# Vario_Kobo_TOP.net
KiCad netlist of a schematic drawn in EAGLE
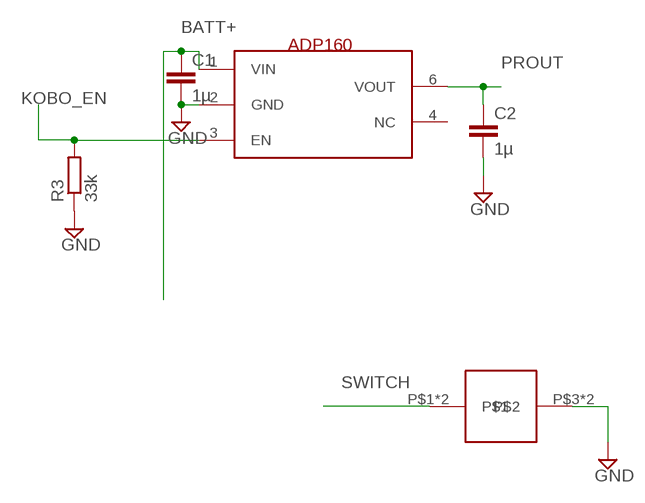
[diagram p0: schematic, sheet 1]
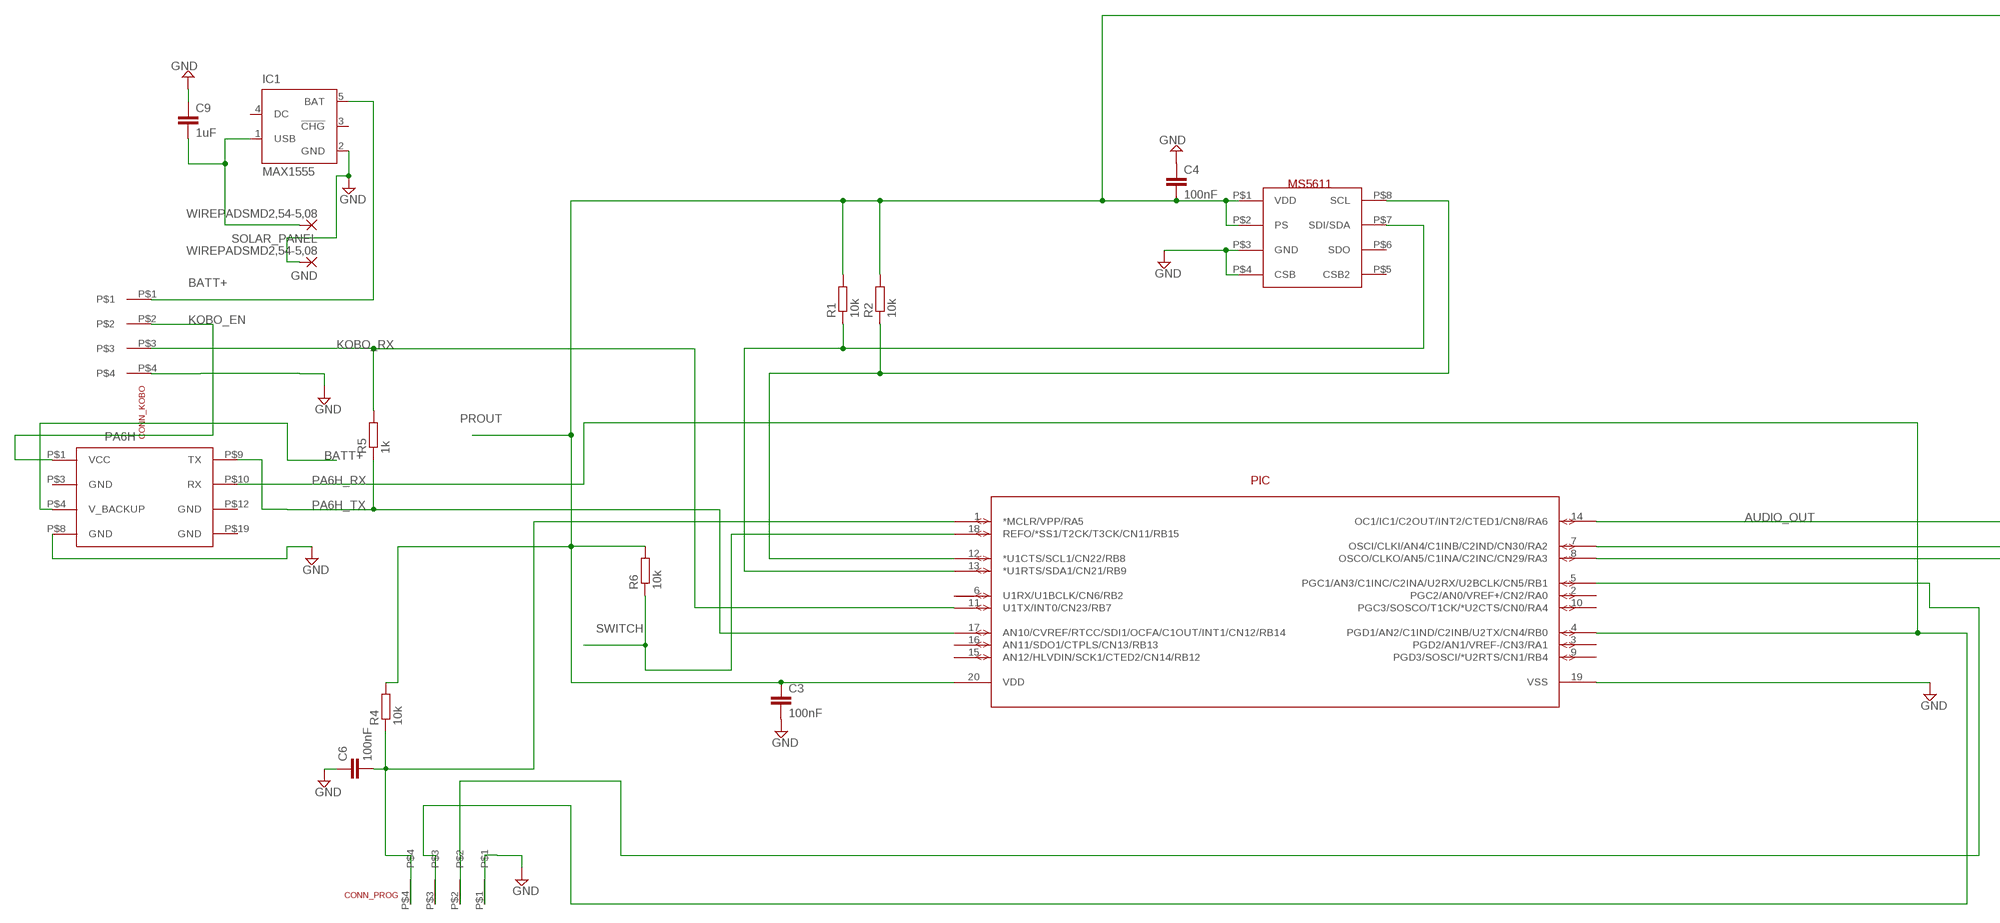
[diagram p1: schematic, sheet 2, part 1 of 2]
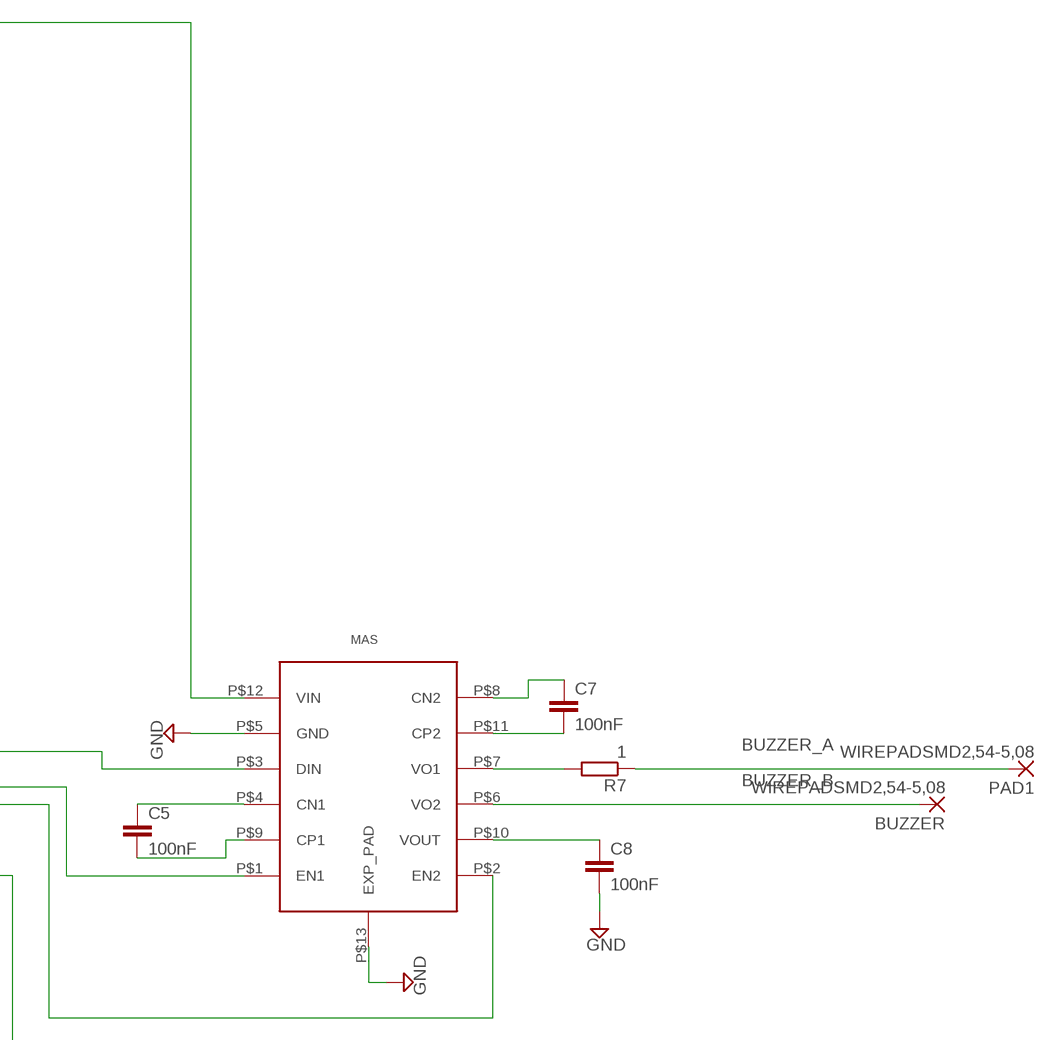
[diagram p2: schematic, sheet 2, part 2 of 2]

(export (version "E")
  (design (tool "Eeschema 10.0.6"))
  (components
    (comp (ref "ADP160")
      (value "ADP160/161/162/163")
      (footprint "eagle-import:TSOT23-6_DDC")
      (libsource (lib "eagle-import") (part "ADP160/161/162/163"))
    )
    (comp (ref "BUTTON")
      (value "LSH_BASE")
      (footprint "eagle-import:LSH_BASE")
      (libsource (lib "eagle-import") (part "LSH_BASE"))
    )
    (comp (ref "C1")
      (value "1µ")
      (footprint "eagle-import:C0603")
      (libsource (lib "eagle-import") (part "C-EUC0603"))
    )
    (comp (ref "C2")
      (value "1µ")
      (footprint "eagle-import:C0603")
      (libsource (lib "eagle-import") (part "C-EUC0603"))
    )
    (comp (ref "R3")
      (value "33k")
      (footprint "eagle-import:R0603")
      (libsource (lib "eagle-import") (part "R-EU_R0603"))
    )
    (comp (ref "BUZZER")
      (value "WIREPADSMD2,54-5,08")
      (footprint "eagle-import:SMD2,54-5,08")
      (libsource (lib "eagle-import") (part "WIREPADSMD2,54-5,08"))
    )
    (comp (ref "C3")
      (value "100nF")
      (footprint "eagle-import:C0603")
      (libsource (lib "eagle-import") (part "C-EUC0603"))
    )
    (comp (ref "C4")
      (value "100nF")
      (footprint "eagle-import:C0603")
      (libsource (lib "eagle-import") (part "C-EUC0603"))
    )
    (comp (ref "C5")
      (value "100nF")
      (footprint "eagle-import:C0603")
      (libsource (lib "eagle-import") (part "C-EUC0603"))
    )
    (comp (ref "C6")
      (value "100nF")
      (footprint "eagle-import:C0603")
      (libsource (lib "eagle-import") (part "C-EUC0603"))
    )
    (comp (ref "C7")
      (value "100nF")
      (footprint "eagle-import:C0603")
      (libsource (lib "eagle-import") (part "C-EUC0603"))
    )
    (comp (ref "C8")
      (value "100nF")
      (footprint "eagle-import:C0603")
      (libsource (lib "eagle-import") (part "C-EUC0603"))
    )
    (comp (ref "C9")
      (value "1uF")
      (footprint "eagle-import:C0603")
      (libsource (lib "eagle-import") (part "C-EUC0603"))
    )
    (comp (ref "CONN_KOBO")
      (value "PICO-EZMATE4")
      (footprint "eagle-import:PICO-EZMATE4-PCB")
      (libsource (lib "eagle-import") (part "PICO-EZMATE4"))
    )
    (comp (ref "CONN_PROG")
      (value "PICO-EZMATE4")
      (footprint "eagle-import:PICO-EZMATE4-PCB")
      (libsource (lib "eagle-import") (part "PICO-EZMATE4"))
    )
    (comp (ref "GND")
      (value "WIREPADSMD2,54-5,08")
      (footprint "eagle-import:SMD2,54-5,08")
      (libsource (lib "eagle-import") (part "WIREPADSMD2,54-5,08"))
    )
    (comp (ref "IC1")
      (value "MAX1555")
      (footprint "eagle-import:SOT23-5L")
      (fields (field (name "MF") "MAXIM") (field (name "MPN") "MAX1555EZK+T"))
      (libsource (lib "eagle-import") (part "MAX1555"))
    )
    (comp (ref "MAS")
      (value "MAS6240")
      (footprint "eagle-import:QFN12_3X3")
      (libsource (lib "eagle-import") (part "MAS6240"))
    )
    (comp (ref "MS5611")
      (value "MS5607PACKAGED")
      (footprint "eagle-import:MS5607-02BA03")
      (libsource (lib "eagle-import") (part "MS5607PACKAGED"))
    )
    (comp (ref "PA6H")
      (value "PA6H")
      (footprint "eagle-import:PA6H_PRINT")
      (libsource (lib "eagle-import") (part "PA6H"))
    )
    (comp (ref "PAD1")
      (value "WIREPADSMD2,54-5,08")
      (footprint "eagle-import:SMD2,54-5,08")
      (libsource (lib "eagle-import") (part "WIREPADSMD2,54-5,08"))
    )
    (comp (ref "PIC")
      (value "PIC24F16KA101-X_")
      (footprint "eagle-import:SSOP20_MC")
      (libsource (lib "eagle-import") (part "PIC24F16KA101-X_"))
    )
    (comp (ref "R1")
      (value "10k")
      (footprint "eagle-import:R0603")
      (libsource (lib "eagle-import") (part "R-EU_R0603"))
    )
    (comp (ref "R2")
      (value "10k")
      (footprint "eagle-import:R0603")
      (libsource (lib "eagle-import") (part "R-EU_R0603"))
    )
    (comp (ref "R4")
      (value "10k")
      (footprint "eagle-import:R0603")
      (libsource (lib "eagle-import") (part "R-EU_R0603"))
    )
    (comp (ref "R5")
      (value "1k")
      (footprint "eagle-import:R0603")
      (libsource (lib "eagle-import") (part "R-EU_R0603"))
    )
    (comp (ref "R6")
      (value "10k")
      (footprint "eagle-import:R0603")
      (libsource (lib "eagle-import") (part "R-EU_R0603"))
    )
    (comp (ref "R7")
      (value "1")
      (footprint "eagle-import:R0603")
      (libsource (lib "eagle-import") (part "R-EU_R0603"))
    )
    (comp (ref "SOLAR_PANEL")
      (value "WIREPADSMD2,54-5,08")
      (footprint "eagle-import:SMD2,54-5,08")
      (libsource (lib "eagle-import") (part "WIREPADSMD2,54-5,08"))
    )
  )
  (nets
    (net (code "1") (name "AUDIO_OUT") (class "Default")
      (node (ref "MAS") (pin "P$3") (pinfunction "DIN_P$3") (pintype "bidirectional"))
      (node (ref "PIC") (pin "14") (pinfunction "OC1/IC1/C2OUT/INT2/CTED1/CN8/RA6_14") (pintype "passive"))
    )
    (net (code "2") (name "BATT+") (class "Default")
      (node (ref "ADP160") (pin "1") (pinfunction "VIN_1") (pintype "tri_state"))
      (node (ref "C1") (pin "1") (pinfunction "1_1") (pintype "passive"))
      (node (ref "CONN_KOBO") (pin "P$1") (pinfunction "P$1_P$1") (pintype "bidirectional"))
      (node (ref "IC1") (pin "5") (pinfunction "BAT_5") (pintype "passive"))
      (node (ref "PA6H") (pin "P$4") (pinfunction "V_BACKUP_P$4") (pintype "bidirectional"))
    )
    (net (code "3") (name "BUZZER_A") (class "Default")
      (node (ref "PAD1") (pin "1") (pinfunction "P_1") (pintype "passive"))
      (node (ref "R7") (pin "1") (pinfunction "1_1") (pintype "passive"))
    )
    (net (code "4") (name "BUZZER_B") (class "Default")
      (node (ref "BUZZER") (pin "1") (pinfunction "P_1") (pintype "passive"))
      (node (ref "MAS") (pin "P$6") (pinfunction "VO2_P$6") (pintype "bidirectional"))
    )
    (net (code "5") (name "GND") (class "Default")
      (node (ref "ADP160") (pin "2") (pinfunction "GND_2") (pintype "power_in"))
      (node (ref "BUTTON") (pin "P$3") (pinfunction "P$2_P$3") (pintype "bidirectional"))
      (node (ref "BUTTON") (pin "P$4") (pinfunction "P$2_P$4") (pintype "bidirectional"))
      (node (ref "C1") (pin "2") (pinfunction "2_2") (pintype "passive"))
      (node (ref "C2") (pin "2") (pinfunction "2_2") (pintype "passive"))
      (node (ref "C3") (pin "2") (pinfunction "2_2") (pintype "passive"))
      (node (ref "C4") (pin "1") (pinfunction "1_1") (pintype "passive"))
      (node (ref "C6") (pin "1") (pinfunction "1_1") (pintype "passive"))
      (node (ref "C8") (pin "2") (pinfunction "2_2") (pintype "passive"))
      (node (ref "C9") (pin "1") (pinfunction "1_1") (pintype "passive"))
      (node (ref "CONN_KOBO") (pin "P$4") (pinfunction "P$4_P$4") (pintype "bidirectional"))
      (node (ref "CONN_PROG") (pin "P$1") (pinfunction "P$1_P$1") (pintype "bidirectional"))
      (node (ref "GND") (pin "1") (pinfunction "P_1") (pintype "passive"))
      (node (ref "IC1") (pin "2") (pinfunction "GND_2") (pintype "power_in"))
      (node (ref "MAS") (pin "P$13") (pinfunction "EXP_PAD_P$13") (pintype "bidirectional"))
      (node (ref "MAS") (pin "P$5") (pinfunction "GND_P$5") (pintype "bidirectional"))
      (node (ref "MS5611") (pin "P$3") (pinfunction "GND_P$3") (pintype "power_in"))
      (node (ref "MS5611") (pin "P$4") (pinfunction "CSB_P$4") (pintype "input"))
      (node (ref "PA6H") (pin "P$8") (pinfunction "GND_P$8") (pintype "bidirectional"))
      (node (ref "PIC") (pin "19") (pinfunction "VSS_19") (pintype "passive"))
      (node (ref "R3") (pin "1") (pinfunction "1_1") (pintype "passive"))
    )
    (net (code "6") (name "KOBO_EN") (class "Default")
      (node (ref "ADP160") (pin "3") (pinfunction "EN_3") (pintype "input"))
      (node (ref "CONN_KOBO") (pin "P$2") (pinfunction "P$2_P$2") (pintype "bidirectional"))
      (node (ref "PA6H") (pin "P$1") (pinfunction "VCC_P$1") (pintype "bidirectional"))
      (node (ref "R3") (pin "2") (pinfunction "2_2") (pintype "passive"))
    )
    (net (code "7") (name "KOBO_RX") (class "Default")
      (node (ref "CONN_KOBO") (pin "P$3") (pinfunction "P$3_P$3") (pintype "bidirectional"))
      (node (ref "PIC") (pin "11") (pinfunction "U1TX/INT0/CN23/RB7_11") (pintype "passive"))
      (node (ref "R5") (pin "2") (pinfunction "2_2") (pintype "passive"))
    )
    (net (code "8") (name "Net-(IC1-USB)") (class "Default")
      (node (ref "C9") (pin "2") (pinfunction "2_2") (pintype "passive"))
      (node (ref "IC1") (pin "1") (pinfunction "USB_1") (pintype "input"))
      (node (ref "SOLAR_PANEL") (pin "1") (pinfunction "P_1") (pintype "passive"))
    )
    (net (code "9") (name "Net-(MAS-CN1)") (class "Default")
      (node (ref "C5") (pin "1") (pinfunction "1_1") (pintype "passive"))
      (node (ref "MAS") (pin "P$4") (pinfunction "CN1_P$4") (pintype "bidirectional"))
    )
    (net (code "10") (name "Net-(MAS-CN2)") (class "Default")
      (node (ref "C7") (pin "1") (pinfunction "1_1") (pintype "passive"))
      (node (ref "MAS") (pin "P$8") (pinfunction "CN2_P$8") (pintype "bidirectional"))
    )
    (net (code "11") (name "Net-(MAS-CP1)") (class "Default")
      (node (ref "C5") (pin "2") (pinfunction "2_2") (pintype "passive"))
      (node (ref "MAS") (pin "P$9") (pinfunction "CP1_P$9") (pintype "bidirectional"))
    )
    (net (code "12") (name "Net-(MAS-CP2)") (class "Default")
      (node (ref "C7") (pin "2") (pinfunction "2_2") (pintype "passive"))
      (node (ref "MAS") (pin "P$11") (pinfunction "CP2_P$11") (pintype "bidirectional"))
    )
    (net (code "13") (name "Net-(MAS-EN1)") (class "Default")
      (node (ref "MAS") (pin "P$1") (pinfunction "EN1_P$1") (pintype "bidirectional"))
      (node (ref "PIC") (pin "7") (pinfunction "OSCI/CLKI/AN4/C1INB/C2IND/CN30/RA2_7") (pintype "passive"))
    )
    (net (code "14") (name "Net-(MAS-EN2)") (class "Default")
      (node (ref "MAS") (pin "P$2") (pinfunction "EN2_P$2") (pintype "bidirectional"))
      (node (ref "PIC") (pin "8") (pinfunction "OSCO/CLKO/AN5/C1INA/C2INC/CN29/RA3_8") (pintype "passive"))
    )
    (net (code "15") (name "Net-(MAS-VO1)") (class "Default")
      (node (ref "MAS") (pin "P$7") (pinfunction "VO1_P$7") (pintype "bidirectional"))
      (node (ref "R7") (pin "2") (pinfunction "2_2") (pintype "passive"))
    )
    (net (code "16") (name "Net-(MAS-VOUT)") (class "Default")
      (node (ref "C8") (pin "1") (pinfunction "1_1") (pintype "passive"))
      (node (ref "MAS") (pin "P$10") (pinfunction "VOUT_P$10") (pintype "bidirectional"))
    )
    (net (code "17") (name "Net-(MS5611-SCL)") (class "Default")
      (node (ref "MS5611") (pin "P$8") (pinfunction "SCL_P$8") (pintype "input"))
      (node (ref "PIC") (pin "12") (pinfunction "*U1CTS/SCL1/CN22/RB8_12") (pintype "passive"))
      (node (ref "R2") (pin "1") (pinfunction "1_1") (pintype "passive"))
    )
    (net (code "18") (name "Net-(MS5611-SDI{slash}SDA)") (class "Default")
      (node (ref "MS5611") (pin "P$7") (pinfunction "SDI/SDA_P$7") (pintype "bidirectional"))
      (node (ref "PIC") (pin "13") (pinfunction "*U1RTS/SDA1/CN21/RB9_13") (pintype "passive"))
      (node (ref "R1") (pin "1") (pinfunction "1_1") (pintype "passive"))
    )
    (net (code "19") (name "Net-(PIC-*MCLR{slash}VPP{slash}RA5)") (class "Default")
      (node (ref "C6") (pin "2") (pinfunction "2_2") (pintype "passive"))
      (node (ref "CONN_PROG") (pin "P$4") (pinfunction "P$4_P$4") (pintype "bidirectional"))
      (node (ref "PIC") (pin "1") (pinfunction "*MCLR/VPP/RA5_1") (pintype "passive"))
      (node (ref "R4") (pin "1") (pinfunction "1_1") (pintype "passive"))
    )
    (net (code "20") (name "Net-(PIC-PGC1{slash}AN3{slash}C1INC{slash}C2INA{slash}U2RX{slash}U2BCLK{slash}CN5{slash}RB1)") (class "Default")
      (node (ref "CONN_PROG") (pin "P$2") (pinfunction "P$2_P$2") (pintype "bidirectional"))
      (node (ref "PIC") (pin "5") (pinfunction "PGC1/AN3/C1INC/C2INA/U2RX/U2BCLK/CN5/RB1_5") (pintype "passive"))
    )
    (net (code "21") (name "PA6H_RX") (class "Default")
      (node (ref "CONN_PROG") (pin "P$3") (pinfunction "P$3_P$3") (pintype "bidirectional"))
      (node (ref "PA6H") (pin "P$10") (pinfunction "RX_P$10") (pintype "bidirectional"))
      (node (ref "PIC") (pin "4") (pinfunction "PGD1/AN2/C1IND/C2INB/U2TX/CN4/RB0_4") (pintype "passive"))
    )
    (net (code "22") (name "PA6H_TX") (class "Default")
      (node (ref "PA6H") (pin "P$9") (pinfunction "TX_P$9") (pintype "bidirectional"))
      (node (ref "PIC") (pin "17") (pinfunction "AN10/CVREF/RTCC/SDI1/OCFA/C1OUT/INT1/CN12/RB14_17") (pintype "passive"))
      (node (ref "R5") (pin "1") (pinfunction "1_1") (pintype "passive"))
    )
    (net (code "23") (name "PROUT") (class "Default")
      (node (ref "ADP160") (pin "6") (pinfunction "VOUT_6") (pintype "bidirectional"))
      (node (ref "C2") (pin "1") (pinfunction "1_1") (pintype "passive"))
      (node (ref "C3") (pin "1") (pinfunction "1_1") (pintype "passive"))
      (node (ref "C4") (pin "2") (pinfunction "2_2") (pintype "passive"))
      (node (ref "MAS") (pin "P$12") (pinfunction "VIN_P$12") (pintype "bidirectional"))
      (node (ref "MS5611") (pin "P$1") (pinfunction "VDD_P$1") (pintype "power_in"))
      (node (ref "MS5611") (pin "P$2") (pinfunction "PS_P$2") (pintype "input"))
      (node (ref "PIC") (pin "20") (pinfunction "VDD_20") (pintype "passive"))
      (node (ref "R1") (pin "2") (pinfunction "2_2") (pintype "passive"))
      (node (ref "R2") (pin "2") (pinfunction "2_2") (pintype "passive"))
      (node (ref "R4") (pin "2") (pinfunction "2_2") (pintype "passive"))
      (node (ref "R6") (pin "2") (pinfunction "2_2") (pintype "passive"))
    )
    (net (code "24") (name "SWITCH") (class "Default")
      (node (ref "BUTTON") (pin "P$1") (pinfunction "P$1_P$1") (pintype "bidirectional"))
      (node (ref "BUTTON") (pin "P$2") (pinfunction "P$1_P$2") (pintype "bidirectional"))
      (node (ref "PIC") (pin "18") (pinfunction "REFO/*SS1/T2CK/T3CK/CN11/RB15_18") (pintype "passive"))
      (node (ref "R6") (pin "1") (pinfunction "1_1") (pintype "passive"))
    )
    (net (code "25") (name "unconnected-(ADP160-NC-Pad4)") (class "Default")
      (node (ref "ADP160") (pin "4") (pinfunction "NC_4") (pintype "no_connect"))
    )
    (net (code "26") (name "unconnected-(IC1-DC-Pad4)") (class "Default")
      (node (ref "IC1") (pin "4") (pinfunction "DC_4") (pintype "input"))
    )
    (net (code "27") (name "unconnected-(IC1-~{CHG}-Pad3)") (class "Default")
      (node (ref "IC1") (pin "3") (pinfunction "~{CHG}_3") (pintype "output"))
    )
    (net (code "28") (name "unconnected-(MS5611-CSB2-PadP$5)") (class "Default")
      (node (ref "MS5611") (pin "P$5") (pinfunction "CSB2_P$5") (pintype "input"))
    )
    (net (code "29") (name "unconnected-(MS5611-SDO-PadP$6)") (class "Default")
      (node (ref "MS5611") (pin "P$6") (pinfunction "SDO_P$6") (pintype "output"))
    )
    (net (code "30") (name "unconnected-(PA6H-GND-PadP$3)") (class "Default")
      (node (ref "PA6H") (pin "P$3") (pinfunction "GND_P$3") (pintype "bidirectional"))
    )
    (net (code "31") (name "unconnected-(PA6H-GND-PadP$12)") (class "Default")
      (node (ref "PA6H") (pin "P$12") (pinfunction "GND_P$12") (pintype "bidirectional"))
    )
    (net (code "32") (name "unconnected-(PA6H-GND-PadP$19)") (class "Default")
      (node (ref "PA6H") (pin "P$19") (pinfunction "GND_P$19") (pintype "bidirectional"))
    )
    (net (code "33") (name "unconnected-(PIC-AN11{slash}SDO1{slash}CTPLS{slash}CN13{slash}RB13-Pad16)") (class "Default")
      (node (ref "PIC") (pin "16") (pinfunction "AN11/SDO1/CTPLS/CN13/RB13_16") (pintype "passive"))
    )
    (net (code "34") (name "unconnected-(PIC-AN12{slash}HLVDIN{slash}SCK1{slash}CTED2{slash}CN14{slash}RB12-Pad15)") (class "Default")
      (node (ref "PIC") (pin "15") (pinfunction "AN12/HLVDIN/SCK1/CTED2/CN14/RB12_15") (pintype "passive"))
    )
    (net (code "35") (name "unconnected-(PIC-PGC2{slash}AN0{slash}VREF+{slash}CN2{slash}RA0-Pad2)") (class "Default")
      (node (ref "PIC") (pin "2") (pinfunction "PGC2/AN0/VREF+/CN2/RA0_2") (pintype "passive"))
    )
    (net (code "36") (name "unconnected-(PIC-PGC3{slash}SOSCO{slash}T1CK{slash}*U2CTS{slash}CN0{slash}RA4-Pad10)") (class "Default")
      (node (ref "PIC") (pin "10") (pinfunction "PGC3/SOSCO/T1CK/*U2CTS/CN0/RA4_10") (pintype "passive"))
    )
    (net (code "37") (name "unconnected-(PIC-PGD2{slash}AN1{slash}VREF-{slash}CN3{slash}RA1-Pad3)") (class "Default")
      (node (ref "PIC") (pin "3") (pinfunction "PGD2/AN1/VREF-/CN3/RA1_3") (pintype "passive"))
    )
    (net (code "38") (name "unconnected-(PIC-PGD3{slash}SOSCI{slash}*U2RTS{slash}CN1{slash}RB4-Pad9)") (class "Default")
      (node (ref "PIC") (pin "9") (pinfunction "PGD3/SOSCI/*U2RTS/CN1/RB4_9") (pintype "passive"))
    )
    (net (code "39") (name "unconnected-(PIC-U1RX{slash}U1BCLK{slash}CN6{slash}RB2-Pad6)") (class "Default")
      (node (ref "PIC") (pin "6") (pinfunction "U1RX/U1BCLK/CN6/RB2_6") (pintype "passive"))
    )
  )
)
